# placa_teste_av.net
KiCad netlist of a schematic drawn in EAGLE
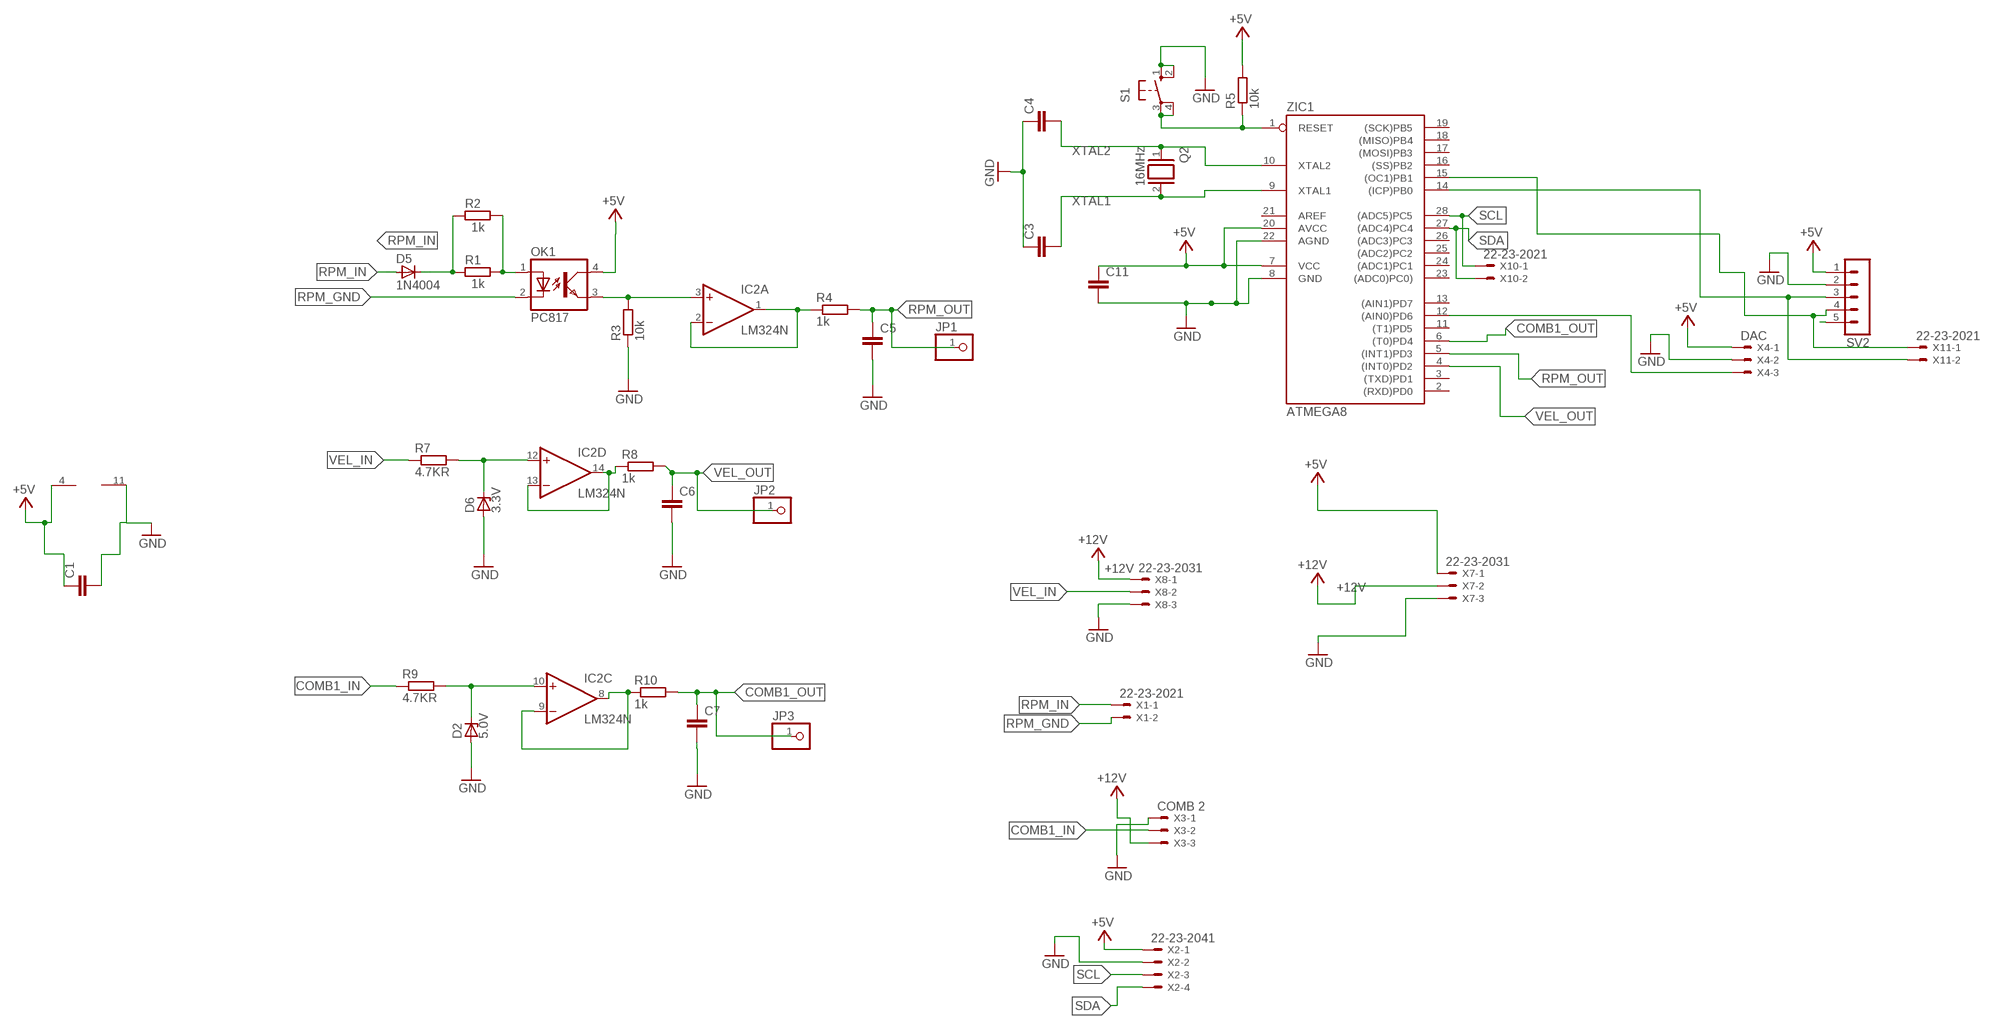
[diagram p0: schematic, sheet 1]

(export (version "E")
  (design (tool "Eeschema 10.0.6"))
  (components
    (comp (ref "C1")
      (value "C5/2.5")
      (footprint "eagle-import:C5B2.5")
      (libsource (lib "eagle-import") (part "C5/2.5"))
    )
    (comp (ref "C3")
      (value "C-EU025-024X044")
      (footprint "eagle-import:C025-024X044")
      (libsource (lib "eagle-import") (part "C-EU025-024X044"))
    )
    (comp (ref "C4")
      (value "C-EU025-024X044")
      (footprint "eagle-import:C025-024X044")
      (libsource (lib "eagle-import") (part "C-EU025-024X044"))
    )
    (comp (ref "C5")
      (value "C5/2.5")
      (footprint "eagle-import:C5B2.5")
      (libsource (lib "eagle-import") (part "C5/2.5"))
    )
    (comp (ref "C6")
      (value "C5/2.5")
      (footprint "eagle-import:C5B2.5")
      (libsource (lib "eagle-import") (part "C5/2.5"))
    )
    (comp (ref "C7")
      (value "C5/2.5")
      (footprint "eagle-import:C5B2.5")
      (libsource (lib "eagle-import") (part "C5/2.5"))
    )
    (comp (ref "C11")
      (value "C5/2.5")
      (footprint "eagle-import:C5B2.5")
      (libsource (lib "eagle-import") (part "C5/2.5"))
    )
    (comp (ref "D2")
      (value "5.0V")
      (footprint "eagle-import:DO34Z7")
      (libsource (lib "eagle-import") (part "ZENER-DIODEDO34-7"))
    )
    (comp (ref "D5")
      (value "1N4004")
      (footprint "eagle-import:DO41-10")
      (libsource (lib "eagle-import") (part "1N4004"))
    )
    (comp (ref "D6")
      (value "3.3V")
      (footprint "eagle-import:DO34Z7")
      (libsource (lib "eagle-import") (part "ZENER-DIODEDO34-7"))
    )
    (comp (ref "IC2")
      (value "LM324N")
      (footprint "eagle-import:DIL14")
      (libsource (lib "eagle-import") (part "LM324N"))
    )
    (comp (ref "JP1")
      (value "PINHD-1X1")
      (footprint "eagle-import:1X01")
      (libsource (lib "eagle-import") (part "PINHD-1X1"))
    )
    (comp (ref "JP2")
      (value "PINHD-1X1")
      (footprint "eagle-import:1X01")
      (libsource (lib "eagle-import") (part "PINHD-1X1"))
    )
    (comp (ref "JP3")
      (value "PINHD-1X1")
      (footprint "eagle-import:1X01")
      (libsource (lib "eagle-import") (part "PINHD-1X1"))
    )
    (comp (ref "OK1")
      (value "PC817")
      (footprint "eagle-import:DIL04")
      (fields (field (name "MPN") "PC817X4J000F"))
      (libsource (lib "eagle-import") (part "PC817"))
    )
    (comp (ref "Q2")
      (value "16MHz")
      (footprint "eagle-import:QS")
      (libsource (lib "eagle-import") (part "XTAL/S"))
    )
    (comp (ref "R1")
      (value "1k")
      (footprint "eagle-import:0207_7")
      (libsource (lib "eagle-import") (part "R-EU_0207/7"))
    )
    (comp (ref "R2")
      (value "1k")
      (footprint "eagle-import:0207_7")
      (libsource (lib "eagle-import") (part "R-EU_0207/7"))
    )
    (comp (ref "R3")
      (value "10k")
      (footprint "eagle-import:0207_7")
      (libsource (lib "eagle-import") (part "R-EU_0207/7"))
    )
    (comp (ref "R4")
      (value "1k")
      (footprint "eagle-import:0207_7")
      (libsource (lib "eagle-import") (part "R-EU_0207/7"))
    )
    (comp (ref "R5")
      (value "10k")
      (footprint "eagle-import:0207_7")
      (libsource (lib "eagle-import") (part "R-EU_0207/7"))
    )
    (comp (ref "R7")
      (value "4.7KR")
      (footprint "eagle-import:0207_7")
      (libsource (lib "eagle-import") (part "R-EU_0207/7"))
    )
    (comp (ref "R8")
      (value "1k")
      (footprint "eagle-import:0207_7")
      (libsource (lib "eagle-import") (part "R-EU_0207/7"))
    )
    (comp (ref "R9")
      (value "4.7KR")
      (footprint "eagle-import:0207_7")
      (libsource (lib "eagle-import") (part "R-EU_0207/7"))
    )
    (comp (ref "R10")
      (value "1k")
      (footprint "eagle-import:0207_7")
      (libsource (lib "eagle-import") (part "R-EU_0207/7"))
    )
    (comp (ref "S1")
      (value "10-XX")
      (footprint "eagle-import:B3F-10XX")
      (fields (field (name "MPN") "B3F-1000"))
      (libsource (lib "eagle-import") (part "10-XX"))
    )
    (comp (ref "SV2")
      (value "MA05-1")
      (footprint "eagle-import:MA05-1")
      (libsource (lib "eagle-import") (part "MA05-1"))
    )
    (comp (ref "X1")
      (value "22-23-2021")
      (footprint "eagle-import:22-23-2021")
      (fields (field (name "MF") "MOLEX"))
      (libsource (lib "eagle-import") (part "22-23-2021"))
    )
    (comp (ref "X2")
      (value "22-23-2041")
      (footprint "eagle-import:22-23-2041")
      (fields (field (name "MF") "MOLEX"))
      (libsource (lib "eagle-import") (part "22-23-2041"))
    )
    (comp (ref "X3")
      (value "COMB 2")
      (footprint "eagle-import:22-23-2031")
      (fields (field (name "MF") "MOLEX") (field (name "MPN") "22-23-2031"))
      (libsource (lib "eagle-import") (part "22-23-2031"))
    )
    (comp (ref "X4")
      (value "DAC")
      (footprint "eagle-import:22-23-2031")
      (fields (field (name "MF") "MOLEX") (field (name "MPN") "22-23-2031"))
      (libsource (lib "eagle-import") (part "22-23-2031"))
    )
    (comp (ref "X7")
      (value "22-23-2031")
      (footprint "eagle-import:22-23-2031")
      (fields (field (name "MF") "MOLEX"))
      (libsource (lib "eagle-import") (part "22-23-2031"))
    )
    (comp (ref "X8")
      (value "22-23-2031")
      (footprint "eagle-import:22-23-2031")
      (fields (field (name "MF") "MOLEX"))
      (libsource (lib "eagle-import") (part "22-23-2031"))
    )
    (comp (ref "X10")
      (value "22-23-2021")
      (footprint "eagle-import:22-23-2021")
      (fields (field (name "MF") "MOLEX"))
      (libsource (lib "eagle-import") (part "22-23-2021"))
    )
    (comp (ref "X11")
      (value "22-23-2021")
      (footprint "eagle-import:22-23-2021")
      (fields (field (name "MF") "MOLEX"))
      (libsource (lib "eagle-import") (part "22-23-2021"))
    )
    (comp (ref "ZIC1")
      (value "ATMEGA8")
      (footprint "eagle-import:DIL28-3")
      (libsource (lib "eagle-import") (part "AT90S4433P"))
    )
  )
  (nets
    (net (code "1") (name "+5V") (class "Default")
      (node (ref "C1") (pin "1") (pinfunction "1_1") (pintype "passive"))
      (node (ref "C11") (pin "1") (pinfunction "1_1") (pintype "passive"))
      (node (ref "IC2") (pin "4") (pinfunction "V+_4") (pintype "power_in"))
      (node (ref "OK1") (pin "4") (pinfunction "COL_4") (pintype "passive"))
      (node (ref "R5") (pin "2") (pinfunction "2_2") (pintype "passive"))
      (node (ref "SV2") (pin "1") (pinfunction "1_1") (pintype "passive"))
      (node (ref "X2") (pin "1") (pinfunction "S_1") (pintype "passive"))
      (node (ref "X4") (pin "1") (pinfunction "S_1") (pintype "passive"))
      (node (ref "X7") (pin "1") (pinfunction "S_1") (pintype "passive"))
      (node (ref "ZIC1") (pin "20") (pinfunction "AVCC_20") (pintype "power_in"))
      (node (ref "ZIC1") (pin "7") (pinfunction "VCC_7") (pintype "power_in"))
    )
    (net (code "2") (name "+12V") (class "Default")
      (node (ref "X3") (pin "3") (pinfunction "S_3") (pintype "passive"))
      (node (ref "X7") (pin "2") (pinfunction "S_2") (pintype "passive"))
      (node (ref "X8") (pin "1") (pinfunction "S_1") (pintype "passive"))
    )
    (net (code "3") (name "/XTAL1") (class "Default")
      (node (ref "C3") (pin "2") (pinfunction "2_2") (pintype "passive"))
      (node (ref "Q2") (pin "2") (pinfunction "2_2") (pintype "passive"))
      (node (ref "ZIC1") (pin "9") (pinfunction "XTAL1_9") (pintype "bidirectional"))
    )
    (net (code "4") (name "/XTAL2") (class "Default")
      (node (ref "C4") (pin "2") (pinfunction "2_2") (pintype "passive"))
      (node (ref "Q2") (pin "1") (pinfunction "1_1") (pintype "passive"))
      (node (ref "ZIC1") (pin "10") (pinfunction "XTAL2_10") (pintype "bidirectional"))
    )
    (net (code "5") (name "COMB1_IN") (class "Default")
      (node (ref "R9") (pin "1") (pinfunction "1_1") (pintype "passive"))
      (node (ref "X3") (pin "2") (pinfunction "S_2") (pintype "passive"))
    )
    (net (code "6") (name "COMB1_OUT") (class "Default")
      (node (ref "C7") (pin "1") (pinfunction "1_1") (pintype "passive"))
      (node (ref "JP3") (pin "1") (pinfunction "1_1") (pintype "passive"))
      (node (ref "R10") (pin "2") (pinfunction "2_2") (pintype "passive"))
      (node (ref "ZIC1") (pin "6") (pinfunction "(T0)PD4_6") (pintype "bidirectional"))
    )
    (net (code "7") (name "GND") (class "Default")
      (node (ref "C1") (pin "2") (pinfunction "2_2") (pintype "passive"))
      (node (ref "C11") (pin "2") (pinfunction "2_2") (pintype "passive"))
      (node (ref "C3") (pin "1") (pinfunction "1_1") (pintype "passive"))
      (node (ref "C4") (pin "1") (pinfunction "1_1") (pintype "passive"))
      (node (ref "C5") (pin "2") (pinfunction "2_2") (pintype "passive"))
      (node (ref "C6") (pin "2") (pinfunction "2_2") (pintype "passive"))
      (node (ref "C7") (pin "2") (pinfunction "2_2") (pintype "passive"))
      (node (ref "D2") (pin "A") (pinfunction "A_A") (pintype "passive"))
      (node (ref "D6") (pin "A") (pinfunction "A_A") (pintype "passive"))
      (node (ref "IC2") (pin "11") (pinfunction "V-_11") (pintype "power_in"))
      (node (ref "R3") (pin "1") (pinfunction "1_1") (pintype "passive"))
      (node (ref "S1") (pin "1") (pinfunction "S_1") (pintype "passive"))
      (node (ref "S1") (pin "2") (pinfunction "S1_2") (pintype "passive"))
      (node (ref "SV2") (pin "2") (pinfunction "2_2") (pintype "passive"))
      (node (ref "X2") (pin "2") (pinfunction "S_2") (pintype "passive"))
      (node (ref "X3") (pin "1") (pinfunction "S_1") (pintype "passive"))
      (node (ref "X4") (pin "2") (pinfunction "S_2") (pintype "passive"))
      (node (ref "X7") (pin "3") (pinfunction "S_3") (pintype "passive"))
      (node (ref "X8") (pin "3") (pinfunction "S_3") (pintype "passive"))
      (node (ref "ZIC1") (pin "22") (pinfunction "AGND_22") (pintype "power_in"))
      (node (ref "ZIC1") (pin "8") (pinfunction "GND_8") (pintype "power_in"))
    )
    (net (code "8") (name "Net-(D5-PadC)") (class "Default")
      (node (ref "D5") (pin "C") (pinfunction "C_C") (pintype "passive"))
      (node (ref "R1") (pin "1") (pinfunction "1_1") (pintype "passive"))
      (node (ref "R2") (pin "1") (pinfunction "1_1") (pintype "passive"))
    )
    (net (code "9") (name "Net-(IC2A-+IN)") (class "Default")
      (node (ref "IC2") (pin "3") (pinfunction "+IN_3") (pintype "input"))
      (node (ref "OK1") (pin "3") (pinfunction "EMIT_3") (pintype "passive"))
      (node (ref "R3") (pin "2") (pinfunction "2_2") (pintype "passive"))
    )
    (net (code "10") (name "Net-(IC2A--IN)") (class "Default")
      (node (ref "IC2") (pin "1") (pinfunction "OUT_1") (pintype "output"))
      (node (ref "IC2") (pin "2") (pinfunction "-IN_2") (pintype "input"))
      (node (ref "R4") (pin "1") (pinfunction "1_1") (pintype "passive"))
    )
    (net (code "11") (name "Net-(IC2C-+IN)") (class "Default")
      (node (ref "D2") (pin "C") (pinfunction "C_C") (pintype "passive"))
      (node (ref "IC2") (pin "10") (pinfunction "+IN_10") (pintype "input"))
      (node (ref "R9") (pin "2") (pinfunction "2_2") (pintype "passive"))
    )
    (net (code "12") (name "Net-(IC2C--IN)") (class "Default")
      (node (ref "IC2") (pin "8") (pinfunction "OUT_8") (pintype "output"))
      (node (ref "IC2") (pin "9") (pinfunction "-IN_9") (pintype "input"))
      (node (ref "R10") (pin "1") (pinfunction "1_1") (pintype "passive"))
    )
    (net (code "13") (name "Net-(IC2D-+IN)") (class "Default")
      (node (ref "D6") (pin "C") (pinfunction "C_C") (pintype "passive"))
      (node (ref "IC2") (pin "12") (pinfunction "+IN_12") (pintype "input"))
      (node (ref "R7") (pin "2") (pinfunction "2_2") (pintype "passive"))
    )
    (net (code "14") (name "Net-(IC2D--IN)") (class "Default")
      (node (ref "IC2") (pin "13") (pinfunction "-IN_13") (pintype "input"))
      (node (ref "IC2") (pin "14") (pinfunction "OUT_14") (pintype "output"))
      (node (ref "R8") (pin "1") (pinfunction "1_1") (pintype "passive"))
    )
    (net (code "15") (name "Net-(OK1-A)") (class "Default")
      (node (ref "OK1") (pin "1") (pinfunction "A_1") (pintype "passive"))
      (node (ref "R1") (pin "2") (pinfunction "2_2") (pintype "passive"))
      (node (ref "R2") (pin "2") (pinfunction "2_2") (pintype "passive"))
    )
    (net (code "16") (name "Net-(S1-P)") (class "Default")
      (node (ref "R5") (pin "1") (pinfunction "1_1") (pintype "passive"))
      (node (ref "S1") (pin "3") (pinfunction "P_3") (pintype "passive"))
      (node (ref "S1") (pin "4") (pinfunction "P1_4") (pintype "passive"))
      (node (ref "ZIC1") (pin "1") (pinfunction "RESET_1") (pintype "input"))
    )
    (net (code "17") (name "Net-(X4C-S)") (class "Default")
      (node (ref "X4") (pin "3") (pinfunction "S_3") (pintype "passive"))
      (node (ref "ZIC1") (pin "12") (pinfunction "(AIN0)PD6_12") (pintype "bidirectional"))
    )
    (net (code "18") (name "Net-(X11A-S)") (class "Default")
      (node (ref "SV2") (pin "4") (pinfunction "4_4") (pintype "passive"))
      (node (ref "X11") (pin "1") (pinfunction "S_1") (pintype "passive"))
      (node (ref "ZIC1") (pin "15") (pinfunction "(OC1)PB1_15") (pintype "bidirectional"))
    )
    (net (code "19") (name "Net-(X11B-S)") (class "Default")
      (node (ref "SV2") (pin "3") (pinfunction "3_3") (pintype "passive"))
      (node (ref "X11") (pin "2") (pinfunction "S_2") (pintype "passive"))
      (node (ref "ZIC1") (pin "14") (pinfunction "(ICP)PB0_14") (pintype "bidirectional"))
    )
    (net (code "20") (name "RPM_GND") (class "Default")
      (node (ref "OK1") (pin "2") (pinfunction "C_2") (pintype "passive"))
      (node (ref "X1") (pin "2") (pinfunction "S_2") (pintype "passive"))
    )
    (net (code "21") (name "RPM_IN") (class "Default")
      (node (ref "D5") (pin "A") (pinfunction "A_A") (pintype "passive"))
      (node (ref "X1") (pin "1") (pinfunction "S_1") (pintype "passive"))
    )
    (net (code "22") (name "RPM_OUT") (class "Default")
      (node (ref "C5") (pin "1") (pinfunction "1_1") (pintype "passive"))
      (node (ref "JP1") (pin "1") (pinfunction "1_1") (pintype "passive"))
      (node (ref "R4") (pin "2") (pinfunction "2_2") (pintype "passive"))
      (node (ref "ZIC1") (pin "5") (pinfunction "(INT1)PD3_5") (pintype "bidirectional"))
    )
    (net (code "23") (name "SCL") (class "Default")
      (node (ref "X10") (pin "1") (pinfunction "S_1") (pintype "passive"))
      (node (ref "X2") (pin "3") (pinfunction "S_3") (pintype "passive"))
      (node (ref "ZIC1") (pin "28") (pinfunction "(ADC5)PC5_28") (pintype "bidirectional"))
    )
    (net (code "24") (name "SDA") (class "Default")
      (node (ref "X10") (pin "2") (pinfunction "S_2") (pintype "passive"))
      (node (ref "X2") (pin "4") (pinfunction "S_4") (pintype "passive"))
      (node (ref "ZIC1") (pin "27") (pinfunction "(ADC4)PC4_27") (pintype "bidirectional"))
    )
    (net (code "25") (name "VEL_IN") (class "Default")
      (node (ref "R7") (pin "1") (pinfunction "1_1") (pintype "passive"))
      (node (ref "X8") (pin "2") (pinfunction "S_2") (pintype "passive"))
    )
    (net (code "26") (name "VEL_OUT") (class "Default")
      (node (ref "C6") (pin "1") (pinfunction "1_1") (pintype "passive"))
      (node (ref "JP2") (pin "1") (pinfunction "1_1") (pintype "passive"))
      (node (ref "R8") (pin "2") (pinfunction "2_2") (pintype "passive"))
      (node (ref "ZIC1") (pin "4") (pinfunction "(INT0)PD2_4") (pintype "bidirectional"))
    )
    (net (code "27") (name "unconnected-(SV2-Pad5)") (class "Default")
      (node (ref "SV2") (pin "5") (pinfunction "5_5") (pintype "passive"))
    )
    (net (code "28") (name "unconnected-(ZIC1-(ADC0)PC0)-Pad23)") (class "Default")
      (node (ref "ZIC1") (pin "23") (pinfunction "(ADC0)PC0)_23") (pintype "bidirectional"))
    )
    (net (code "29") (name "unconnected-(ZIC1-(ADC1)PC1-Pad24)") (class "Default")
      (node (ref "ZIC1") (pin "24") (pinfunction "(ADC1)PC1_24") (pintype "bidirectional"))
    )
    (net (code "30") (name "unconnected-(ZIC1-(ADC2)PC2-Pad25)") (class "Default")
      (node (ref "ZIC1") (pin "25") (pinfunction "(ADC2)PC2_25") (pintype "bidirectional"))
    )
    (net (code "31") (name "unconnected-(ZIC1-(ADC3)PC3-Pad26)") (class "Default")
      (node (ref "ZIC1") (pin "26") (pinfunction "(ADC3)PC3_26") (pintype "bidirectional"))
    )
    (net (code "32") (name "unconnected-(ZIC1-(AIN1)PD7-Pad13)") (class "Default")
      (node (ref "ZIC1") (pin "13") (pinfunction "(AIN1)PD7_13") (pintype "bidirectional"))
    )
    (net (code "33") (name "unconnected-(ZIC1-(MISO)PB4-Pad18)") (class "Default")
      (node (ref "ZIC1") (pin "18") (pinfunction "(MISO)PB4_18") (pintype "bidirectional"))
    )
    (net (code "34") (name "unconnected-(ZIC1-(MOSI)PB3-Pad17)") (class "Default")
      (node (ref "ZIC1") (pin "17") (pinfunction "(MOSI)PB3_17") (pintype "bidirectional"))
    )
    (net (code "35") (name "unconnected-(ZIC1-(RXD)PD0-Pad2)") (class "Default")
      (node (ref "ZIC1") (pin "2") (pinfunction "(RXD)PD0_2") (pintype "bidirectional"))
    )
    (net (code "36") (name "unconnected-(ZIC1-(SCK)PB5-Pad19)") (class "Default")
      (node (ref "ZIC1") (pin "19") (pinfunction "(SCK)PB5_19") (pintype "bidirectional"))
    )
    (net (code "37") (name "unconnected-(ZIC1-(SS)PB2-Pad16)") (class "Default")
      (node (ref "ZIC1") (pin "16") (pinfunction "(SS)PB2_16") (pintype "bidirectional"))
    )
    (net (code "38") (name "unconnected-(ZIC1-(T1)PD5-Pad11)") (class "Default")
      (node (ref "ZIC1") (pin "11") (pinfunction "(T1)PD5_11") (pintype "bidirectional"))
    )
    (net (code "39") (name "unconnected-(ZIC1-(TXD)PD1-Pad3)") (class "Default")
      (node (ref "ZIC1") (pin "3") (pinfunction "(TXD)PD1_3") (pintype "bidirectional"))
    )
    (net (code "40") (name "unconnected-(ZIC1-AREF-Pad21)") (class "Default")
      (node (ref "ZIC1") (pin "21") (pinfunction "AREF_21") (pintype "passive"))
    )
  )
)
